# emoc.net
KiCad netlist of a schematic drawn in Altium Designer
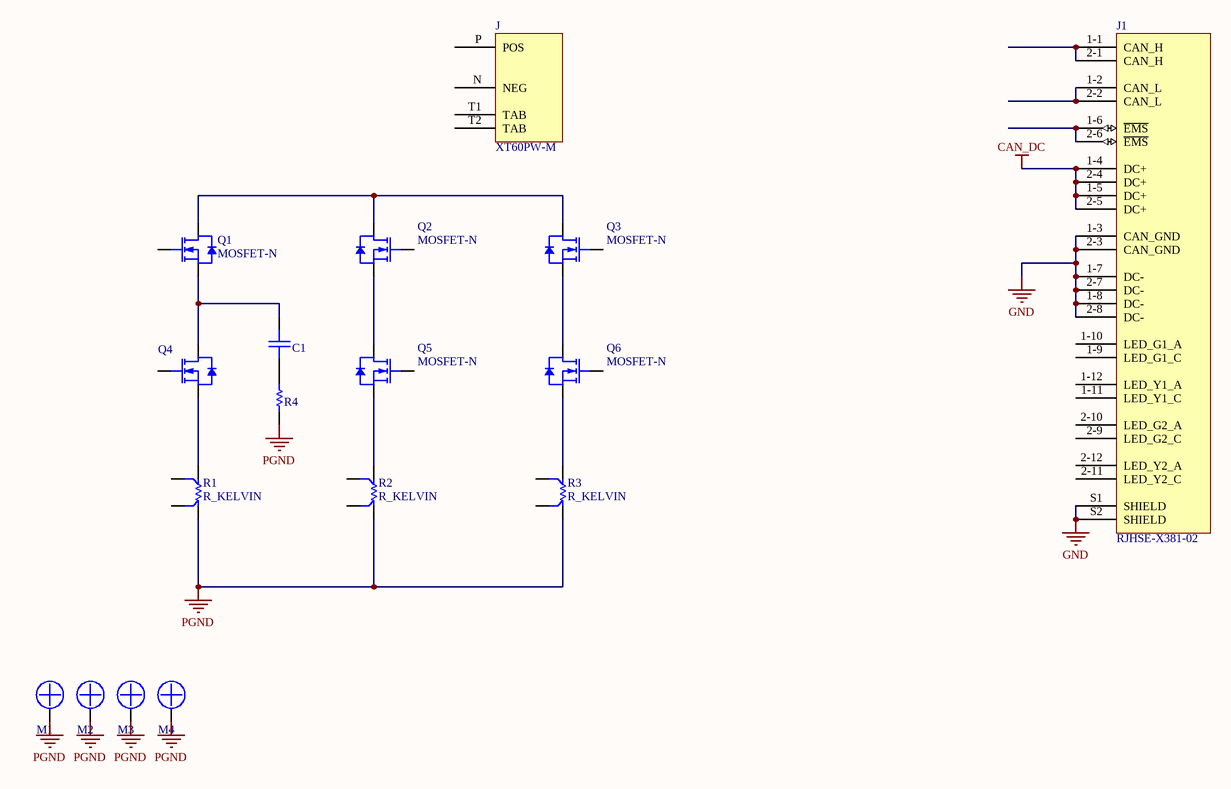
[diagram p0: emoc.SchDoc]

(export (version "E")
  (design (tool "Eeschema 10.0.6"))
  (components
    (comp (ref "C1") (value "~") (footprint "C0603N") (libsource (lib "libysk") (part "C")))
    (comp (ref "J")
      (value "XT60PW-M")
      (footprint "XT60PW-M")
      (description "XT60, Male, THT, R/A")
      (libsource (lib "libysk") (part "XT60PW-M"))
    )
    (comp (ref "J1")
      (value "RJHSE-X381-02")
      (footprint "RJHSE-X38X-02")
      (libsource (lib "libysk") (part "RJHSE-X381-02"))
    )
    (comp (ref "M1")
      (value "Mounting_Screw")
      (footprint "MOUNT_HOLE_3.2")
      (libsource (lib "libysk") (part "Mounting_Screw"))
    )
    (comp (ref "M2")
      (value "Mounting_Screw")
      (footprint "MOUNT_HOLE_3.2")
      (libsource (lib "libysk") (part "Mounting_Screw"))
    )
    (comp (ref "M3")
      (value "Mounting_Screw")
      (footprint "MOUNT_HOLE_3.2")
      (libsource (lib "libysk") (part "Mounting_Screw"))
    )
    (comp (ref "M4")
      (value "Mounting_Screw")
      (footprint "MOUNT_HOLE_3.2")
      (libsource (lib "libysk") (part "Mounting_Screw"))
    )
    (comp (ref "Q1")
      (value "MOSFET-N")
      (footprint "DFN-5 (SO-8FL)")
      (libsource (lib "libysk") (part "MOSFET-N"))
    )
    (comp (ref "Q2")
      (value "MOSFET-N")
      (footprint "DFN-5 (SO-8FL)")
      (libsource (lib "libysk") (part "MOSFET-N"))
    )
    (comp (ref "Q3")
      (value "MOSFET-N")
      (footprint "DFN-5 (SO-8FL)")
      (libsource (lib "libysk") (part "MOSFET-N"))
    )
    (comp (ref "Q4")
      (value "MOSFET-N")
      (footprint "DFN-5 (SO-8FL)")
      (libsource (lib "libysk") (part "MOSFET-N"))
    )
    (comp (ref "Q5")
      (value "MOSFET-N")
      (footprint "DFN-5 (SO-8FL)")
      (libsource (lib "libysk") (part "MOSFET-N"))
    )
    (comp (ref "Q6")
      (value "MOSFET-N")
      (footprint "DFN-5 (SO-8FL)")
      (libsource (lib "libysk") (part "MOSFET-N"))
    )
    (comp (ref "R1")
      (value "R_KELVIN")
      (footprint "CSS2H-2512N_KELVIN")
      (libsource (lib "libysk") (part "R_KELVIN"))
    )
    (comp (ref "R2")
      (value "R_KELVIN")
      (footprint "CSS2H-2512N_KELVIN")
      (libsource (lib "libysk") (part "R_KELVIN"))
    )
    (comp (ref "R3")
      (value "R_KELVIN")
      (footprint "CSS2H-2512N_KELVIN")
      (libsource (lib "libysk") (part "R_KELVIN"))
    )
    (comp (ref "R4") (value "~") (footprint "CR0805") (libsource (lib "libysk") (part "R")))
  )
  (nets
    (net (code "1") (name "CAN_DC") (class "Default")
      (node (ref "J1") (pin "1-4") (pinfunction "DC+_1-4") (pintype "passive"))
      (node (ref "J1") (pin "1-5") (pinfunction "DC+_1-5") (pintype "passive"))
      (node (ref "J1") (pin "2-4") (pinfunction "DC+_2-4") (pintype "passive"))
      (node (ref "J1") (pin "2-5") (pinfunction "DC+_2-5") (pintype "passive"))
    )
    (net (code "2") (name "GND") (class "Default")
      (node (ref "J1") (pin "1-3") (pinfunction "CAN_GND_1-3") (pintype "passive"))
      (node (ref "J1") (pin "1-7") (pinfunction "DC-_1-7") (pintype "passive"))
      (node (ref "J1") (pin "1-8") (pinfunction "DC-_1-8") (pintype "passive"))
      (node (ref "J1") (pin "2-3") (pinfunction "CAN_GND_2-3") (pintype "passive"))
      (node (ref "J1") (pin "2-7") (pinfunction "DC-_2-7") (pintype "passive"))
      (node (ref "J1") (pin "2-8") (pinfunction "DC-_2-8") (pintype "passive"))
      (node (ref "J1") (pin "S1") (pinfunction "SHIELD_S1") (pintype "passive"))
      (node (ref "J1") (pin "S2") (pinfunction "SHIELD_S2") (pintype "passive"))
    )
    (net (code "3") (name "Net-(C1-Pad1)") (class "Default")
      (node (ref "C1") (pin "1") (pinfunction "1_1") (pintype "passive"))
      (node (ref "R4") (pin "1") (pinfunction "1_1") (pintype "passive"))
    )
    (net (code "4") (name "Net-(C1-Pad2)") (class "Default")
      (node (ref "C1") (pin "2") (pinfunction "2_2") (pintype "passive"))
      (node (ref "Q1") (pin "S") (pinfunction "S_S") (pintype "passive"))
      (node (ref "Q4") (pin "D") (pinfunction "D_D") (pintype "passive"))
    )
    (net (code "5") (name "Net-(J1-CAN_H-Pad1-1)") (class "Default")
      (node (ref "J1") (pin "1-1") (pinfunction "CAN_H_1-1") (pintype "passive"))
      (node (ref "J1") (pin "2-1") (pinfunction "CAN_H_2-1") (pintype "passive"))
    )
    (net (code "6") (name "Net-(J1-CAN_L-Pad1-2)") (class "Default")
      (node (ref "J1") (pin "1-2") (pinfunction "CAN_L_1-2") (pintype "passive"))
      (node (ref "J1") (pin "2-2") (pinfunction "CAN_L_2-2") (pintype "passive"))
    )
    (net (code "7") (name "Net-(J1-~{EMS}-Pad1-6)") (class "Default")
      (node (ref "J1") (pin "1-6") (pinfunction "~{EMS}_1-6") (pintype "bidirectional"))
      (node (ref "J1") (pin "2-6") (pinfunction "~{EMS}_2-6") (pintype "bidirectional"))
    )
    (net (code "8") (name "Net-(Q1-PadD)") (class "Default")
      (node (ref "Q1") (pin "D") (pinfunction "D_D") (pintype "passive"))
      (node (ref "Q2") (pin "D") (pinfunction "D_D") (pintype "passive"))
      (node (ref "Q3") (pin "D") (pinfunction "D_D") (pintype "passive"))
    )
    (net (code "9") (name "Net-(Q2-PadS)") (class "Default")
      (node (ref "Q2") (pin "S") (pinfunction "S_S") (pintype "passive"))
      (node (ref "Q5") (pin "D") (pinfunction "D_D") (pintype "passive"))
    )
    (net (code "10") (name "Net-(Q3-PadS)") (class "Default")
      (node (ref "Q3") (pin "S") (pinfunction "S_S") (pintype "passive"))
      (node (ref "Q6") (pin "D") (pinfunction "D_D") (pintype "passive"))
    )
    (net (code "11") (name "Net-(Q4-PadS)") (class "Default")
      (node (ref "Q4") (pin "S") (pinfunction "S_S") (pintype "passive"))
      (node (ref "R1") (pin "2") (pinfunction "2_2") (pintype "passive"))
    )
    (net (code "12") (name "Net-(Q5-PadS)") (class "Default")
      (node (ref "Q5") (pin "S") (pinfunction "S_S") (pintype "passive"))
      (node (ref "R2") (pin "2") (pinfunction "2_2") (pintype "passive"))
    )
    (net (code "13") (name "Net-(Q6-PadS)") (class "Default")
      (node (ref "Q6") (pin "S") (pinfunction "S_S") (pintype "passive"))
      (node (ref "R3") (pin "2") (pinfunction "2_2") (pintype "passive"))
    )
    (net (code "14") (name "PGND") (class "Default")
      (node (ref "M1") (pin "1") (pinfunction "1_1") (pintype "passive"))
      (node (ref "M2") (pin "1") (pinfunction "1_1") (pintype "passive"))
      (node (ref "M3") (pin "1") (pinfunction "1_1") (pintype "passive"))
      (node (ref "M4") (pin "1") (pinfunction "1_1") (pintype "passive"))
      (node (ref "R1") (pin "1") (pinfunction "1_1") (pintype "passive"))
      (node (ref "R2") (pin "1") (pinfunction "1_1") (pintype "passive"))
      (node (ref "R3") (pin "1") (pinfunction "1_1") (pintype "passive"))
      (node (ref "R4") (pin "2") (pinfunction "2_2") (pintype "passive"))
    )
    (net (code "15") (name "unconnected-(J-NEG-PadN)") (class "Default")
      (node (ref "J") (pin "N") (pinfunction "NEG_N") (pintype "passive"))
    )
    (net (code "16") (name "unconnected-(J-POS-PadP)") (class "Default")
      (node (ref "J") (pin "P") (pinfunction "POS_P") (pintype "passive"))
    )
    (net (code "17") (name "unconnected-(J-TAB-PadT1)") (class "Default")
      (node (ref "J") (pin "T1") (pinfunction "TAB_T1") (pintype "passive"))
    )
    (net (code "18") (name "unconnected-(J-TAB-PadT2)") (class "Default")
      (node (ref "J") (pin "T2") (pinfunction "TAB_T2") (pintype "passive"))
    )
    (net (code "19") (name "unconnected-(J1-LED_G1_A-Pad1-10)") (class "Default")
      (node (ref "J1") (pin "1-10") (pinfunction "LED_G1_A_1-10") (pintype "passive"))
    )
    (net (code "20") (name "unconnected-(J1-LED_G1_C-Pad1-9)") (class "Default")
      (node (ref "J1") (pin "1-9") (pinfunction "LED_G1_C_1-9") (pintype "passive"))
    )
    (net (code "21") (name "unconnected-(J1-LED_G2_A-Pad2-10)") (class "Default")
      (node (ref "J1") (pin "2-10") (pinfunction "LED_G2_A_2-10") (pintype "passive"))
    )
    (net (code "22") (name "unconnected-(J1-LED_G2_C-Pad2-9)") (class "Default")
      (node (ref "J1") (pin "2-9") (pinfunction "LED_G2_C_2-9") (pintype "passive"))
    )
    (net (code "23") (name "unconnected-(J1-LED_Y1_A-Pad1-12)") (class "Default")
      (node (ref "J1") (pin "1-12") (pinfunction "LED_Y1_A_1-12") (pintype "passive"))
    )
    (net (code "24") (name "unconnected-(J1-LED_Y1_C-Pad1-11)") (class "Default")
      (node (ref "J1") (pin "1-11") (pinfunction "LED_Y1_C_1-11") (pintype "passive"))
    )
    (net (code "25") (name "unconnected-(J1-LED_Y2_A-Pad2-12)") (class "Default")
      (node (ref "J1") (pin "2-12") (pinfunction "LED_Y2_A_2-12") (pintype "passive"))
    )
    (net (code "26") (name "unconnected-(J1-LED_Y2_C-Pad2-11)") (class "Default")
      (node (ref "J1") (pin "2-11") (pinfunction "LED_Y2_C_2-11") (pintype "passive"))
    )
    (net (code "27") (name "unconnected-(Q1-PadG)") (class "Default")
      (node (ref "Q1") (pin "G") (pinfunction "G_G") (pintype "passive"))
    )
    (net (code "28") (name "unconnected-(Q2-PadG)") (class "Default")
      (node (ref "Q2") (pin "G") (pinfunction "G_G") (pintype "passive"))
    )
    (net (code "29") (name "unconnected-(Q3-PadG)") (class "Default")
      (node (ref "Q3") (pin "G") (pinfunction "G_G") (pintype "passive"))
    )
    (net (code "30") (name "unconnected-(Q4-PadG)") (class "Default")
      (node (ref "Q4") (pin "G") (pinfunction "G_G") (pintype "passive"))
    )
    (net (code "31") (name "unconnected-(Q5-PadG)") (class "Default")
      (node (ref "Q5") (pin "G") (pinfunction "G_G") (pintype "passive"))
    )
    (net (code "32") (name "unconnected-(Q6-PadG)") (class "Default")
      (node (ref "Q6") (pin "G") (pinfunction "G_G") (pintype "passive"))
    )
    (net (code "33") (name "unconnected-(R1-Pad3)") (class "Default")
      (node (ref "R1") (pin "3") (pinfunction "3_3") (pintype "passive"))
    )
    (net (code "34") (name "unconnected-(R1-Pad4)") (class "Default")
      (node (ref "R1") (pin "4") (pinfunction "4_4") (pintype "passive"))
    )
    (net (code "35") (name "unconnected-(R2-Pad3)") (class "Default")
      (node (ref "R2") (pin "3") (pinfunction "3_3") (pintype "passive"))
    )
    (net (code "36") (name "unconnected-(R2-Pad4)") (class "Default")
      (node (ref "R2") (pin "4") (pinfunction "4_4") (pintype "passive"))
    )
    (net (code "37") (name "unconnected-(R3-Pad3)") (class "Default")
      (node (ref "R3") (pin "3") (pinfunction "3_3") (pintype "passive"))
    )
    (net (code "38") (name "unconnected-(R3-Pad4)") (class "Default")
      (node (ref "R3") (pin "4") (pinfunction "4_4") (pintype "passive"))
    )
  )
)
